# fc_power_board_v3.net
KiCad netlist of a schematic drawn in EAGLE
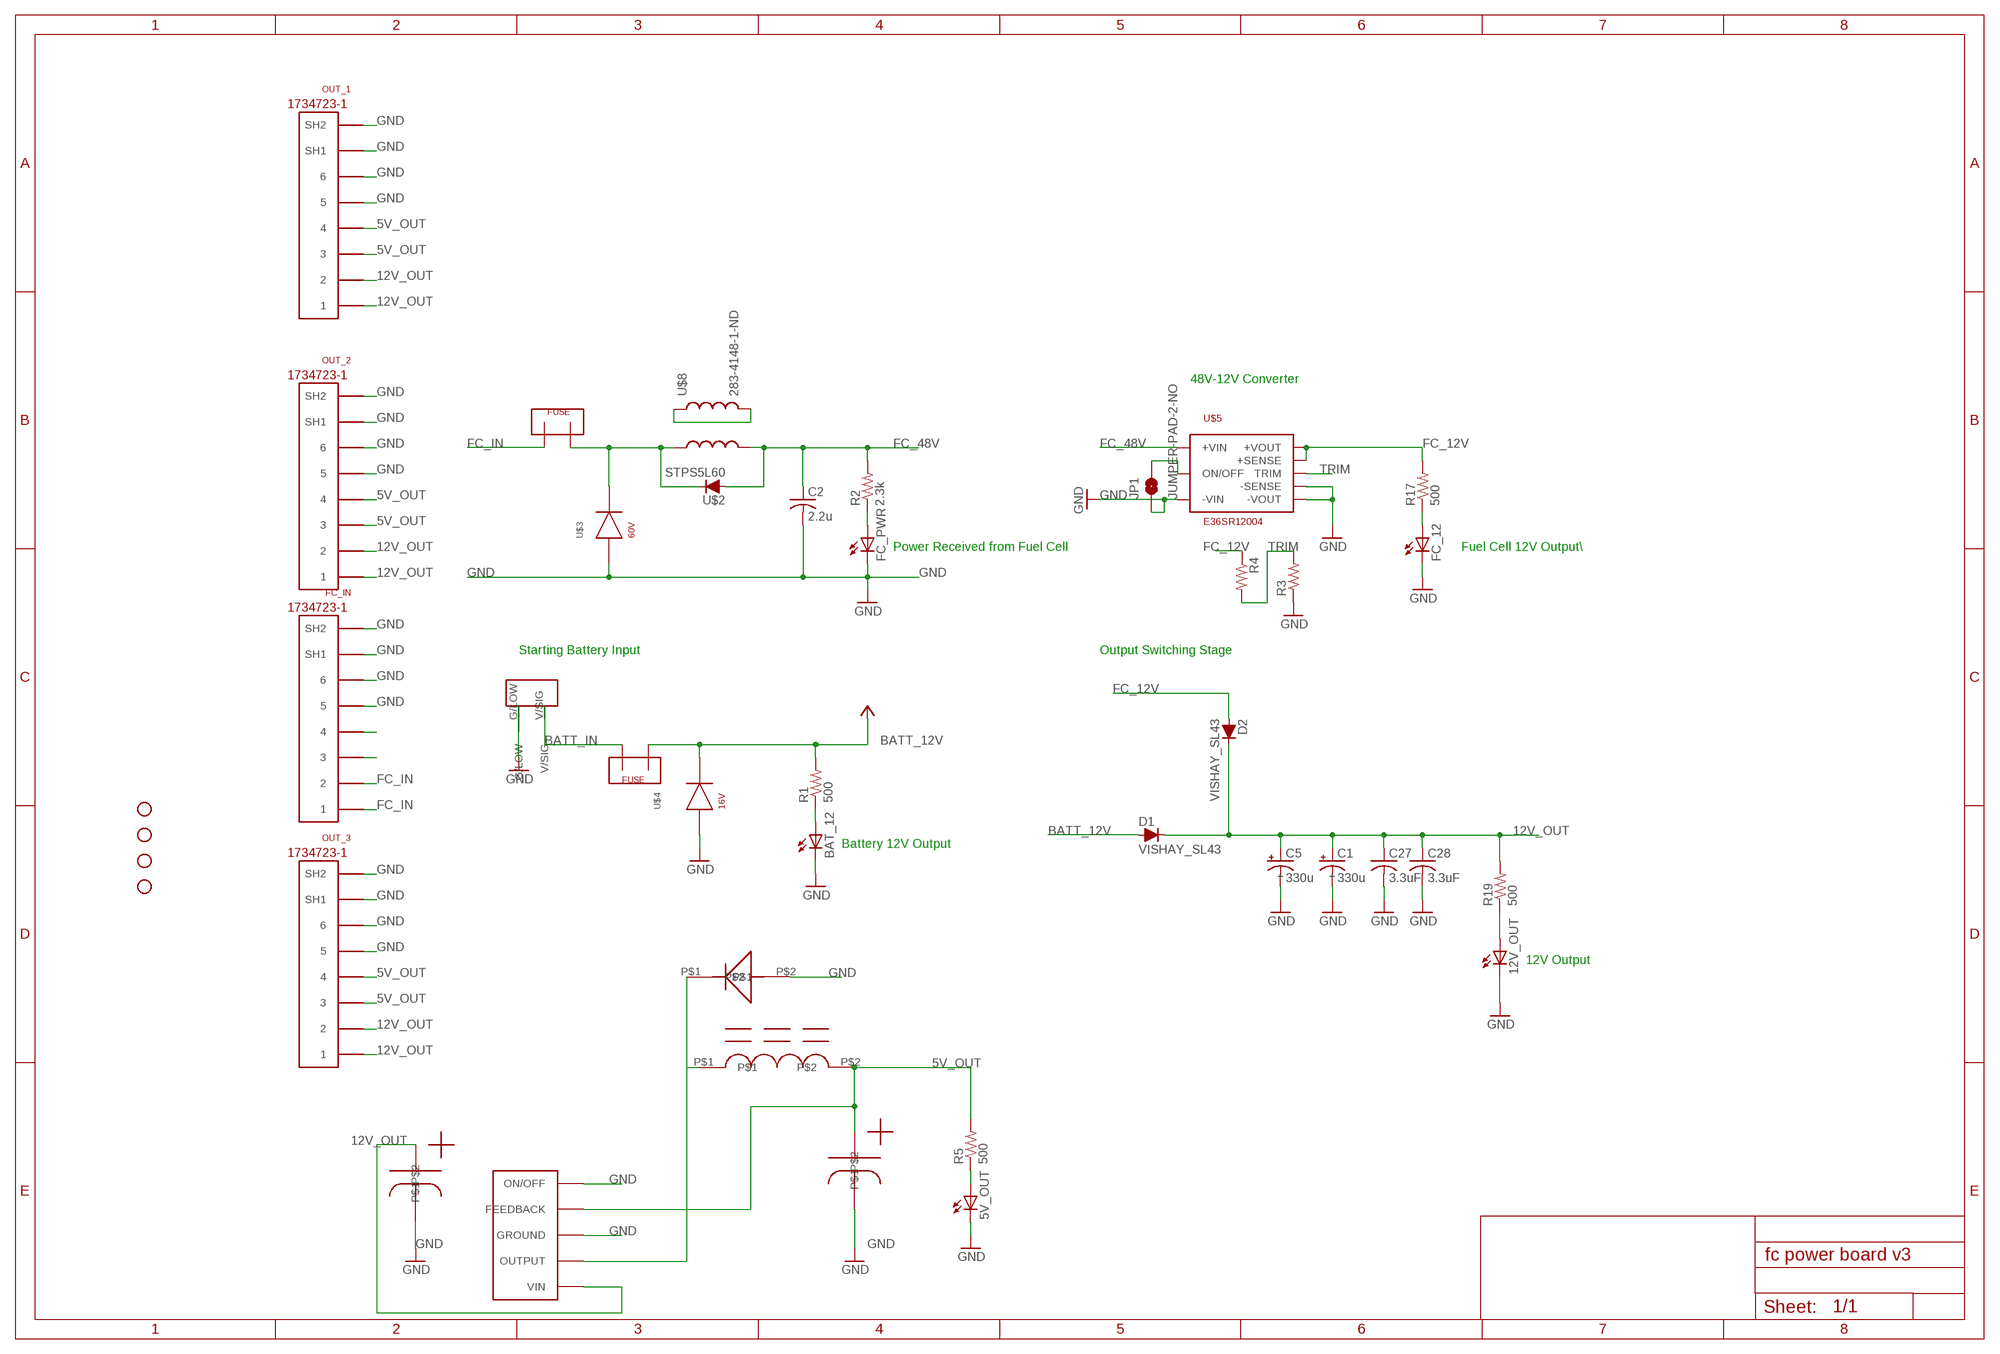
[diagram p0: schematic, sheet 1]

(export (version "E")
  (design (tool "Eeschema 10.0.6"))
  (components
    (comp (ref "5V_OUT")
      (value "LED1206")
      (footprint "eagle-import:LED-1206")
      (libsource (lib "eagle-import") (part "LED1206"))
    )
    (comp (ref "12V_OUT")
      (value "LED1206")
      (footprint "eagle-import:LED-1206")
      (libsource (lib "eagle-import") (part "LED1206"))
    )
    (comp (ref "BATTERY_FUSE")
      (value "FUSEMINI-BLADE")
      (footprint "eagle-import:MINI-BLADE-FUSE")
      (libsource (lib "eagle-import") (part "FUSEMINI-BLADE"))
    )
    (comp (ref "BAT_12")
      (value "LED1206")
      (footprint "eagle-import:LED-1206")
      (libsource (lib "eagle-import") (part "LED1206"))
    )
    (comp (ref "C1")
      (value "330u")
      (footprint "eagle-import:399-6608-ND")
      (libsource (lib "eagle-import") (part "399-6608-ND"))
    )
    (comp (ref "C2")
      (value "2.2u")
      (footprint "eagle-import:C0805")
      (libsource (lib "eagle-import") (part "C-USC0805"))
    )
    (comp (ref "C5")
      (value "330u")
      (footprint "eagle-import:399-6608-ND")
      (libsource (lib "eagle-import") (part "399-6608-ND"))
    )
    (comp (ref "C27")
      (value "3.3uF")
      (footprint "eagle-import:C0805")
      (libsource (lib "eagle-import") (part "C-USC0805"))
    )
    (comp (ref "C28")
      (value "3.3uF")
      (footprint "eagle-import:C0805")
      (libsource (lib "eagle-import") (part "C-USC0805"))
    )
    (comp (ref "D1")
      (value "VISHAY_SL43")
      (footprint "eagle-import:DO-214AB_SMC")
      (libsource (lib "eagle-import") (part "VISHAY_SL43"))
    )
    (comp (ref "D2")
      (value "VISHAY_SL43")
      (footprint "eagle-import:DO-214AB_SMC")
      (libsource (lib "eagle-import") (part "VISHAY_SL43"))
    )
    (comp (ref "FC_12")
      (value "LED1206")
      (footprint "eagle-import:LED-1206")
      (libsource (lib "eagle-import") (part "LED1206"))
    )
    (comp (ref "FC_IN")
      (value "5555140-6")
      (footprint "eagle-import:1734723-1_RJ11")
      (libsource (lib "eagle-import") (part "5555140-6"))
    )
    (comp (ref "FC_PWR")
      (value "LED1206")
      (footprint "eagle-import:LED-1206")
      (libsource (lib "eagle-import") (part "LED1206"))
    )
    (comp (ref "JP1")
      (value "JUMPER-PAD-2-NO")
      (footprint "eagle-import:PAD-JUMPER-2-NO_NO_SILK")
      (libsource (lib "eagle-import") (part "JUMPER-PAD-2-NO"))
    )
    (comp (ref "OUT_1")
      (value "5555140-6")
      (footprint "eagle-import:1734723-1_RJ11")
      (libsource (lib "eagle-import") (part "5555140-6"))
    )
    (comp (ref "OUT_2")
      (value "5555140-6")
      (footprint "eagle-import:1734723-1_RJ11")
      (libsource (lib "eagle-import") (part "5555140-6"))
    )
    (comp (ref "OUT_3")
      (value "5555140-6")
      (footprint "eagle-import:1734723-1_RJ11")
      (libsource (lib "eagle-import") (part "5555140-6"))
    )
    (comp (ref "R1")
      (value "500")
      (footprint "eagle-import:R0805")
      (libsource (lib "eagle-import") (part "resistor_R-US_R0805"))
    )
    (comp (ref "R2")
      (value "2.3k")
      (footprint "eagle-import:R0805")
      (libsource (lib "eagle-import") (part "resistor_R-US_R0805"))
    )
    (comp (ref "R3")
      (value "R-US_R0805")
      (footprint "eagle-import:R0805")
      (libsource (lib "eagle-import") (part "resistor_R-US_R0805"))
    )
    (comp (ref "R4")
      (value "R-US_R0805")
      (footprint "eagle-import:R0805")
      (libsource (lib "eagle-import") (part "resistor_R-US_R0805"))
    )
    (comp (ref "R5")
      (value "500")
      (footprint "eagle-import:R0805")
      (libsource (lib "eagle-import") (part "resistor_R-US_R0805"))
    )
    (comp (ref "R17")
      (value "500")
      (footprint "eagle-import:R0805")
      (libsource (lib "eagle-import") (part "resistor_R-US_R0805"))
    )
    (comp (ref "R19")
      (value "500")
      (footprint "eagle-import:M0805")
      (libsource (lib "eagle-import") (part "R-US_M0805"))
    )
    (comp (ref "STANDOFF1")
      (value "STAND-OFF")
      (footprint "eagle-import:STAND-OFF")
      (libsource (lib "eagle-import") (part "STAND-OFF"))
    )
    (comp (ref "STANDOFF2")
      (value "STAND-OFF")
      (footprint "eagle-import:STAND-OFF")
      (libsource (lib "eagle-import") (part "STAND-OFF"))
    )
    (comp (ref "STANDOFF3")
      (value "STAND-OFF")
      (footprint "eagle-import:STAND-OFF")
      (libsource (lib "eagle-import") (part "STAND-OFF"))
    )
    (comp (ref "STANDOFF4")
      (value "STAND-OFF")
      (footprint "eagle-import:STAND-OFF")
      (libsource (lib "eagle-import") (part "STAND-OFF"))
    )
    (comp (ref "U$1")
      (value "MBR360GOS")
      (footprint "eagle-import:MBR360GOS")
      (libsource (lib "eagle-import") (part "MBR360GOS"))
    )
    (comp (ref "U$2")
      (value "STPS5L60")
      (footprint "eagle-import:STM_SMC")
      (libsource (lib "eagle-import") (part "STPS5L60"))
    )
    (comp (ref "U$3")
      (value "SMBJ60CA")
      (footprint "eagle-import:.277X.089")
      (libsource (lib "eagle-import") (part "SMBJ60CA"))
    )
    (comp (ref "U$4")
      (value "SMAJ16CA")
      (footprint "eagle-import:.25X.07")
      (libsource (lib "eagle-import") (part "SMAJ16CA"))
    )
    (comp (ref "U$5")
      (value "E36SR12004")
      (footprint "eagle-import:2.30X0.90X0.34")
      (libsource (lib "eagle-import") (part "E36SR12004"))
    )
    (comp (ref "U$7")
      (value "FUSEMINI-BLADE")
      (footprint "eagle-import:MINI-BLADE-FUSE")
      (libsource (lib "eagle-import") (part "FUSEMINI-BLADE"))
    )
    (comp (ref "U$8")
      (value "283-4148-1-ND")
      (footprint "eagle-import:283-4148-1-ND")
      (libsource (lib "eagle-import") (part "283-4148-1-ND"))
    )
    (comp (ref "U$9")
      (value "2_PIN_TECONNECTOR")
      (footprint "eagle-import:2_PIN_CONNECT")
      (libsource (lib "eagle-import") (part "2_PIN_TECONNECTOR"))
    )
    (comp (ref "U$13")
      (value "LM2576")
      (footprint "eagle-import:D2PAK-5")
      (libsource (lib "eagle-import") (part "LM2576"))
    )
    (comp (ref "U$14")
      (value "CAPESK107M025AC3AA")
      (footprint "eagle-import:ESK107M025AC3AA")
      (libsource (lib "eagle-import") (part "CAPESK107M025AC3AA"))
    )
    (comp (ref "U$15")
      (value "CAPESK108M025AH4EA")
      (footprint "eagle-import:ESK108M025AH4EA")
      (libsource (lib "eagle-import") (part "CAPESK108M025AH4EA"))
    )
    (comp (ref "U$16")
      (value "M1418-ND")
      (footprint "eagle-import:M1418-ND")
      (libsource (lib "eagle-import") (part "M1418-ND"))
    )
  )
  (nets
    (net (code "1") (name "+5V") (class "Default")
      (node (ref "BATTERY_FUSE") (pin "OUT") (pinfunction "OUT_OUT") (pintype "bidirectional"))
      (node (ref "D1") (pin "A") (pinfunction "A_A") (pintype "passive"))
      (node (ref "R1") (pin "2") (pinfunction "2_2") (pintype "passive"))
      (node (ref "U$4") (pin "CATHODE") (pinfunction "CATHODE_CATHODE") (pintype "bidirectional"))
    )
    (net (code "2") (name "/5V_OUT") (class "Default")
      (node (ref "OUT_1") (pin "3") (pinfunction "3_3") (pintype "bidirectional"))
      (node (ref "OUT_1") (pin "4") (pinfunction "4_4") (pintype "bidirectional"))
      (node (ref "OUT_2") (pin "3") (pinfunction "3_3") (pintype "bidirectional"))
      (node (ref "OUT_2") (pin "4") (pinfunction "4_4") (pintype "bidirectional"))
      (node (ref "OUT_3") (pin "3") (pinfunction "3_3") (pintype "bidirectional"))
      (node (ref "OUT_3") (pin "4") (pinfunction "4_4") (pintype "bidirectional"))
      (node (ref "R5") (pin "2") (pinfunction "2_2") (pintype "passive"))
      (node (ref "U$13") (pin "4") (pinfunction "FEEDBACK_4") (pintype "bidirectional"))
      (node (ref "U$15") (pin "P$1") (pinfunction "P$1_P$1") (pintype "bidirectional"))
      (node (ref "U$16") (pin "P$2") (pinfunction "P$2_P$2") (pintype "bidirectional"))
    )
    (net (code "3") (name "/12V_OUT") (class "Default")
      (node (ref "C1") (pin "PLUS") (pinfunction "+_PLUS") (pintype "passive"))
      (node (ref "C27") (pin "1") (pinfunction "1_1") (pintype "passive"))
      (node (ref "C28") (pin "1") (pinfunction "1_1") (pintype "passive"))
      (node (ref "C5") (pin "PLUS") (pinfunction "+_PLUS") (pintype "passive"))
      (node (ref "D1") (pin "C") (pinfunction "C_C") (pintype "passive"))
      (node (ref "D2") (pin "C") (pinfunction "C_C") (pintype "passive"))
      (node (ref "OUT_1") (pin "1") (pinfunction "1_1") (pintype "bidirectional"))
      (node (ref "OUT_1") (pin "2") (pinfunction "2_2") (pintype "bidirectional"))
      (node (ref "OUT_2") (pin "1") (pinfunction "1_1") (pintype "bidirectional"))
      (node (ref "OUT_2") (pin "2") (pinfunction "2_2") (pintype "bidirectional"))
      (node (ref "OUT_3") (pin "1") (pinfunction "1_1") (pintype "bidirectional"))
      (node (ref "OUT_3") (pin "2") (pinfunction "2_2") (pintype "bidirectional"))
      (node (ref "R19") (pin "2") (pinfunction "2_2") (pintype "passive"))
      (node (ref "U$13") (pin "1") (pinfunction "VIN_1") (pintype "bidirectional"))
      (node (ref "U$14") (pin "P$1") (pinfunction "P$1_P$1") (pintype "bidirectional"))
    )
    (net (code "4") (name "/BATT_IN") (class "Default")
      (node (ref "BATTERY_FUSE") (pin "IN") (pinfunction "IN_IN") (pintype "bidirectional"))
      (node (ref "U$9") (pin "V/SIG") (pinfunction "V/SIG_V/SIG") (pintype "bidirectional"))
    )
    (net (code "5") (name "/FC_12V") (class "Default")
      (node (ref "D2") (pin "A") (pinfunction "A_A") (pintype "passive"))
      (node (ref "R17") (pin "2") (pinfunction "2_2") (pintype "passive"))
      (node (ref "R4") (pin "1") (pinfunction "1_1") (pintype "passive"))
      (node (ref "U$5") (pin "P$7") (pinfunction "+SENSE_P$7") (pintype "input"))
      (node (ref "U$5") (pin "P$8") (pinfunction "+VOUT_P$8") (pintype "power_in"))
    )
    (net (code "6") (name "/FC_48V") (class "Default")
      (node (ref "C2") (pin "1") (pinfunction "1_1") (pintype "passive"))
      (node (ref "R2") (pin "2") (pinfunction "2_2") (pintype "passive"))
      (node (ref "U$2") (pin "A") (pinfunction "A_A") (pintype "passive"))
      (node (ref "U$5") (pin "P$1") (pinfunction "+VIN_P$1") (pintype "power_in"))
      (node (ref "U$8") (pin "P$3") (pinfunction "2_P$3") (pintype "passive"))
    )
    (net (code "7") (name "/FC_IN") (class "Default")
      (node (ref "FC_IN") (pin "1") (pinfunction "1_1") (pintype "bidirectional"))
      (node (ref "FC_IN") (pin "2") (pinfunction "2_2") (pintype "bidirectional"))
      (node (ref "U$7") (pin "OUT") (pinfunction "OUT_OUT") (pintype "bidirectional"))
    )
    (net (code "8") (name "/TRIM") (class "Default")
      (node (ref "R3") (pin "2") (pinfunction "2_2") (pintype "passive"))
      (node (ref "R4") (pin "2") (pinfunction "2_2") (pintype "passive"))
      (node (ref "U$5") (pin "P$6") (pinfunction "TRIM_P$6") (pintype "bidirectional"))
    )
    (net (code "9") (name "GND") (class "Default")
      (node (ref "12V_OUT") (pin "C") (pinfunction "C_C") (pintype "passive"))
      (node (ref "5V_OUT") (pin "C") (pinfunction "C_C") (pintype "passive"))
      (node (ref "BAT_12") (pin "C") (pinfunction "C_C") (pintype "passive"))
      (node (ref "C1") (pin "MINUS") (pinfunction "-_MINUS") (pintype "passive"))
      (node (ref "C2") (pin "2") (pinfunction "2_2") (pintype "passive"))
      (node (ref "C27") (pin "2") (pinfunction "2_2") (pintype "passive"))
      (node (ref "C28") (pin "2") (pinfunction "2_2") (pintype "passive"))
      (node (ref "C5") (pin "MINUS") (pinfunction "-_MINUS") (pintype "passive"))
      (node (ref "FC_12") (pin "C") (pinfunction "C_C") (pintype "passive"))
      (node (ref "FC_IN") (pin "5") (pinfunction "5_5") (pintype "bidirectional"))
      (node (ref "FC_IN") (pin "6") (pinfunction "6_6") (pintype "bidirectional"))
      (node (ref "FC_IN") (pin "SH1") (pinfunction "SH1_SH1") (pintype "bidirectional"))
      (node (ref "FC_IN") (pin "SH2") (pinfunction "SH2_SH2") (pintype "bidirectional"))
      (node (ref "FC_PWR") (pin "C") (pinfunction "C_C") (pintype "passive"))
      (node (ref "JP1") (pin "1") (pinfunction "1_1") (pintype "passive"))
      (node (ref "OUT_1") (pin "5") (pinfunction "5_5") (pintype "bidirectional"))
      (node (ref "OUT_1") (pin "6") (pinfunction "6_6") (pintype "bidirectional"))
      (node (ref "OUT_1") (pin "SH1") (pinfunction "SH1_SH1") (pintype "bidirectional"))
      (node (ref "OUT_1") (pin "SH2") (pinfunction "SH2_SH2") (pintype "bidirectional"))
      (node (ref "OUT_2") (pin "5") (pinfunction "5_5") (pintype "bidirectional"))
      (node (ref "OUT_2") (pin "6") (pinfunction "6_6") (pintype "bidirectional"))
      (node (ref "OUT_2") (pin "SH1") (pinfunction "SH1_SH1") (pintype "bidirectional"))
      (node (ref "OUT_2") (pin "SH2") (pinfunction "SH2_SH2") (pintype "bidirectional"))
      (node (ref "OUT_3") (pin "5") (pinfunction "5_5") (pintype "bidirectional"))
      (node (ref "OUT_3") (pin "6") (pinfunction "6_6") (pintype "bidirectional"))
      (node (ref "OUT_3") (pin "SH1") (pinfunction "SH1_SH1") (pintype "bidirectional"))
      (node (ref "OUT_3") (pin "SH2") (pinfunction "SH2_SH2") (pintype "bidirectional"))
      (node (ref "R3") (pin "1") (pinfunction "1_1") (pintype "passive"))
      (node (ref "U$1") (pin "P$2") (pinfunction "P$1_P$2") (pintype "bidirectional"))
      (node (ref "U$13") (pin "3") (pinfunction "GROUND_3") (pintype "bidirectional"))
      (node (ref "U$13") (pin "5") (pinfunction "ON/OFF_5") (pintype "bidirectional"))
      (node (ref "U$13") (pin "GROUND") (pinfunction "GROUND_GROUND") (pintype "bidirectional"))
      (node (ref "U$14") (pin "P$2") (pinfunction "P$2_P$2") (pintype "bidirectional"))
      (node (ref "U$15") (pin "P$2") (pinfunction "P$2_P$2") (pintype "bidirectional"))
      (node (ref "U$3") (pin "ANODE") (pinfunction "ANODE_ANODE") (pintype "bidirectional"))
      (node (ref "U$4") (pin "ANODE") (pinfunction "ANODE_ANODE") (pintype "bidirectional"))
      (node (ref "U$5") (pin "P$3") (pinfunction "-VIN_P$3") (pintype "power_in"))
      (node (ref "U$5") (pin "P$4") (pinfunction "-VOUT_P$4") (pintype "power_in"))
      (node (ref "U$5") (pin "P$5") (pinfunction "-SENSE_P$5") (pintype "input"))
      (node (ref "U$9") (pin "G/LOW") (pinfunction "G/LOW_G/LOW") (pintype "bidirectional"))
    )
    (net (code "10") (name "Net-(5V_OUT-PadA)") (class "Default")
      (node (ref "5V_OUT") (pin "A") (pinfunction "A_A") (pintype "passive"))
      (node (ref "R5") (pin "1") (pinfunction "1_1") (pintype "passive"))
    )
    (net (code "11") (name "Net-(12V_OUT-PadA)") (class "Default")
      (node (ref "12V_OUT") (pin "A") (pinfunction "A_A") (pintype "passive"))
      (node (ref "R19") (pin "1") (pinfunction "1_1") (pintype "passive"))
    )
    (net (code "12") (name "Net-(BAT_12-PadA)") (class "Default")
      (node (ref "BAT_12") (pin "A") (pinfunction "A_A") (pintype "passive"))
      (node (ref "R1") (pin "1") (pinfunction "1_1") (pintype "passive"))
    )
    (net (code "13") (name "Net-(FC_12-PadA)") (class "Default")
      (node (ref "FC_12") (pin "A") (pinfunction "A_A") (pintype "passive"))
      (node (ref "R17") (pin "1") (pinfunction "1_1") (pintype "passive"))
    )
    (net (code "14") (name "Net-(FC_PWR-PadA)") (class "Default")
      (node (ref "FC_PWR") (pin "A") (pinfunction "A_A") (pintype "passive"))
      (node (ref "R2") (pin "1") (pinfunction "1_1") (pintype "passive"))
    )
    (net (code "15") (name "Net-(U$1-P$2)") (class "Default")
      (node (ref "U$1") (pin "P$1") (pinfunction "P$2_P$1") (pintype "bidirectional"))
      (node (ref "U$13") (pin "2") (pinfunction "OUTPUT_2") (pintype "bidirectional"))
      (node (ref "U$16") (pin "P$1") (pinfunction "P$1_P$1") (pintype "bidirectional"))
    )
    (net (code "16") (name "Net-(U$5-ON{slash}OFF)") (class "Default")
      (node (ref "JP1") (pin "2") (pinfunction "2_2") (pintype "passive"))
      (node (ref "U$5") (pin "P$2") (pinfunction "ON/OFF_P$2") (pintype "bidirectional"))
    )
    (net (code "17") (name "Net-(U$8-1)") (class "Default")
      (node (ref "U$2") (pin "C") (pinfunction "C_C") (pintype "passive"))
      (node (ref "U$3") (pin "CATHODE") (pinfunction "CATHODE_CATHODE") (pintype "bidirectional"))
      (node (ref "U$7") (pin "IN") (pinfunction "IN_IN") (pintype "bidirectional"))
      (node (ref "U$8") (pin "P$1") (pinfunction "1_P$1") (pintype "passive"))
    )
    (net (code "18") (name "Net-(U$8-3)") (class "Default")
      (node (ref "U$8") (pin "P$2") (pinfunction "3_P$2") (pintype "passive"))
      (node (ref "U$8") (pin "P$4") (pinfunction "4_P$4") (pintype "passive"))
    )
    (net (code "19") (name "unconnected-(FC_IN-Pad3)") (class "Default")
      (node (ref "FC_IN") (pin "3") (pinfunction "3_3") (pintype "bidirectional"))
    )
    (net (code "20") (name "unconnected-(FC_IN-Pad4)") (class "Default")
      (node (ref "FC_IN") (pin "4") (pinfunction "4_4") (pintype "bidirectional"))
    )
  )
)
